# eCog106_BLED.net
KiCad netlist of a schematic drawn in EAGLE
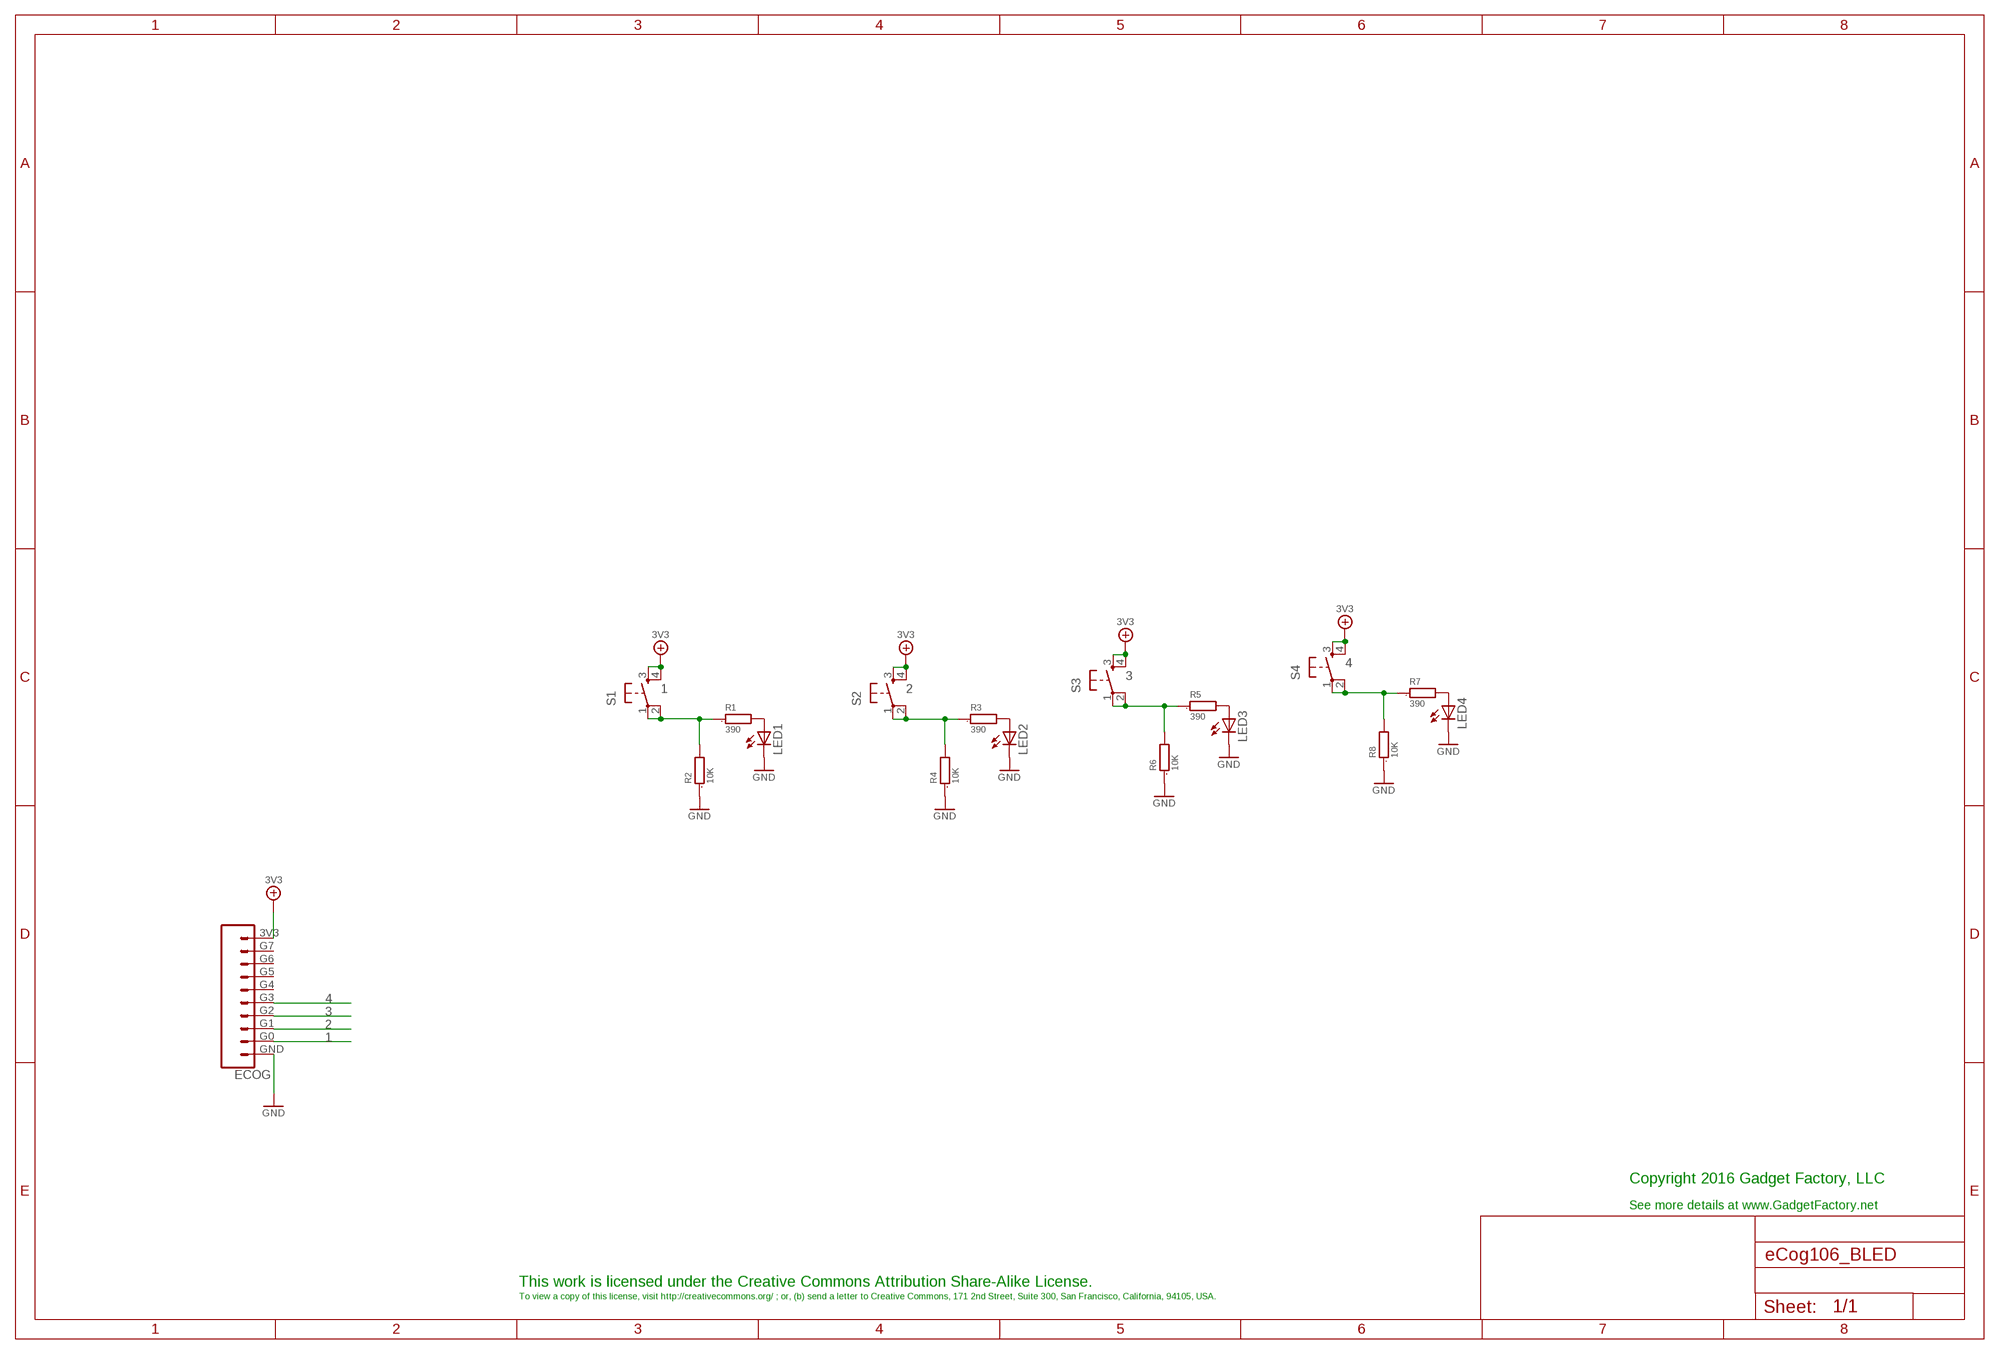
[diagram p0: schematic, sheet 1]

(export (version "E")
  (design (tool "Eeschema 10.0.6"))
  (components
    (comp (ref "ECOG")
      (value "ECOG_GENERAL_ROWECOG_GENERAL_SMD")
      (footprint "eagle-import:ECOG_GENERAL_SMD")
      (libsource (lib "eagle-import") (part "ECOG_GENERAL_ROWECOG_GENERAL_SMD"))
    )
    (comp (ref "LED1")
      (value "LEDCHIP-LED0805")
      (footprint "eagle-import:CHIP-LED0805")
      (libsource (lib "eagle-import") (part "LEDCHIP-LED0805"))
    )
    (comp (ref "LED2")
      (value "LEDCHIP-LED0805")
      (footprint "eagle-import:CHIP-LED0805")
      (libsource (lib "eagle-import") (part "LEDCHIP-LED0805"))
    )
    (comp (ref "LED3")
      (value "LEDCHIP-LED0805")
      (footprint "eagle-import:CHIP-LED0805")
      (libsource (lib "eagle-import") (part "LEDCHIP-LED0805"))
    )
    (comp (ref "LED4")
      (value "LEDCHIP-LED0805")
      (footprint "eagle-import:CHIP-LED0805")
      (libsource (lib "eagle-import") (part "LEDCHIP-LED0805"))
    )
    (comp (ref "R1")
      (value "390")
      (footprint "eagle-import:0805")
      (libsource (lib "eagle-import") (part "R0805"))
    )
    (comp (ref "R2")
      (value "10K")
      (footprint "eagle-import:0805")
      (libsource (lib "eagle-import") (part "R0805"))
    )
    (comp (ref "R3")
      (value "390")
      (footprint "eagle-import:0805")
      (libsource (lib "eagle-import") (part "R0805"))
    )
    (comp (ref "R4")
      (value "10K")
      (footprint "eagle-import:0805")
      (libsource (lib "eagle-import") (part "R0805"))
    )
    (comp (ref "R5")
      (value "390")
      (footprint "eagle-import:0805")
      (libsource (lib "eagle-import") (part "R0805"))
    )
    (comp (ref "R6")
      (value "10K")
      (footprint "eagle-import:0805")
      (libsource (lib "eagle-import") (part "R0805"))
    )
    (comp (ref "R7")
      (value "390")
      (footprint "eagle-import:0805")
      (libsource (lib "eagle-import") (part "R0805"))
    )
    (comp (ref "R8")
      (value "10K")
      (footprint "eagle-import:0805")
      (libsource (lib "eagle-import") (part "R0805"))
    )
    (comp (ref "S1")
      (value "TAC_SWITCHPTH")
      (footprint "eagle-import:TACTILE-PTH")
      (libsource (lib "eagle-import") (part "TAC_SWITCHPTH"))
    )
    (comp (ref "S2")
      (value "TAC_SWITCHPTH")
      (footprint "eagle-import:TACTILE-PTH")
      (libsource (lib "eagle-import") (part "TAC_SWITCHPTH"))
    )
    (comp (ref "S3")
      (value "TAC_SWITCHPTH")
      (footprint "eagle-import:TACTILE-PTH")
      (libsource (lib "eagle-import") (part "TAC_SWITCHPTH"))
    )
    (comp (ref "S4")
      (value "TAC_SWITCHPTH")
      (footprint "eagle-import:TACTILE-PTH")
      (libsource (lib "eagle-import") (part "TAC_SWITCHPTH"))
    )
  )
  (nets
    (net (code "1") (name "/1") (class "Default")
      (node (ref "ECOG") (pin "G0") (pinfunction "G0_G0") (pintype "passive"))
      (node (ref "R1") (pin "1") (pinfunction "1_1") (pintype "passive"))
      (node (ref "R2") (pin "2") (pinfunction "2_2") (pintype "passive"))
      (node (ref "S1") (pin "1") (pinfunction "1_1") (pintype "passive"))
      (node (ref "S1") (pin "2") (pinfunction "2_2") (pintype "passive"))
    )
    (net (code "2") (name "/2") (class "Default")
      (node (ref "ECOG") (pin "G1") (pinfunction "G1_G1") (pintype "passive"))
      (node (ref "R3") (pin "1") (pinfunction "1_1") (pintype "passive"))
      (node (ref "R4") (pin "2") (pinfunction "2_2") (pintype "passive"))
      (node (ref "S2") (pin "1") (pinfunction "1_1") (pintype "passive"))
      (node (ref "S2") (pin "2") (pinfunction "2_2") (pintype "passive"))
    )
    (net (code "3") (name "/3") (class "Default")
      (node (ref "ECOG") (pin "G2") (pinfunction "G2_G2") (pintype "passive"))
      (node (ref "R5") (pin "1") (pinfunction "1_1") (pintype "passive"))
      (node (ref "R6") (pin "2") (pinfunction "2_2") (pintype "passive"))
      (node (ref "S3") (pin "1") (pinfunction "1_1") (pintype "passive"))
      (node (ref "S3") (pin "2") (pinfunction "2_2") (pintype "passive"))
    )
    (net (code "4") (name "/4") (class "Default")
      (node (ref "ECOG") (pin "G3") (pinfunction "G3_G3") (pintype "passive"))
      (node (ref "R7") (pin "1") (pinfunction "1_1") (pintype "passive"))
      (node (ref "R8") (pin "2") (pinfunction "2_2") (pintype "passive"))
      (node (ref "S4") (pin "1") (pinfunction "1_1") (pintype "passive"))
      (node (ref "S4") (pin "2") (pinfunction "2_2") (pintype "passive"))
    )
    (net (code "5") (name "3V3") (class "Default")
      (node (ref "ECOG") (pin "3V3") (pinfunction "3V3_3V3") (pintype "power_in"))
      (node (ref "S1") (pin "3") (pinfunction "3_3") (pintype "passive"))
      (node (ref "S1") (pin "4") (pinfunction "4_4") (pintype "passive"))
      (node (ref "S2") (pin "3") (pinfunction "3_3") (pintype "passive"))
      (node (ref "S2") (pin "4") (pinfunction "4_4") (pintype "passive"))
      (node (ref "S3") (pin "3") (pinfunction "3_3") (pintype "passive"))
      (node (ref "S3") (pin "4") (pinfunction "4_4") (pintype "passive"))
      (node (ref "S4") (pin "3") (pinfunction "3_3") (pintype "passive"))
      (node (ref "S4") (pin "4") (pinfunction "4_4") (pintype "passive"))
    )
    (net (code "6") (name "GND") (class "Default")
      (node (ref "ECOG") (pin "GND") (pinfunction "GND_GND") (pintype "power_in"))
      (node (ref "LED1") (pin "C") (pinfunction "C_C") (pintype "passive"))
      (node (ref "LED2") (pin "C") (pinfunction "C_C") (pintype "passive"))
      (node (ref "LED3") (pin "C") (pinfunction "C_C") (pintype "passive"))
      (node (ref "LED4") (pin "C") (pinfunction "C_C") (pintype "passive"))
      (node (ref "R2") (pin "1") (pinfunction "1_1") (pintype "passive"))
      (node (ref "R4") (pin "1") (pinfunction "1_1") (pintype "passive"))
      (node (ref "R6") (pin "1") (pinfunction "1_1") (pintype "passive"))
      (node (ref "R8") (pin "1") (pinfunction "1_1") (pintype "passive"))
    )
    (net (code "7") (name "Net-(LED1-PadA)") (class "Default")
      (node (ref "LED1") (pin "A") (pinfunction "A_A") (pintype "passive"))
      (node (ref "R1") (pin "2") (pinfunction "2_2") (pintype "passive"))
    )
    (net (code "8") (name "Net-(LED2-PadA)") (class "Default")
      (node (ref "LED2") (pin "A") (pinfunction "A_A") (pintype "passive"))
      (node (ref "R3") (pin "2") (pinfunction "2_2") (pintype "passive"))
    )
    (net (code "9") (name "Net-(LED3-PadA)") (class "Default")
      (node (ref "LED3") (pin "A") (pinfunction "A_A") (pintype "passive"))
      (node (ref "R5") (pin "2") (pinfunction "2_2") (pintype "passive"))
    )
    (net (code "10") (name "Net-(LED4-PadA)") (class "Default")
      (node (ref "LED4") (pin "A") (pinfunction "A_A") (pintype "passive"))
      (node (ref "R7") (pin "2") (pinfunction "2_2") (pintype "passive"))
    )
    (net (code "11") (name "unconnected-(ECOG-PadG4)") (class "Default")
      (node (ref "ECOG") (pin "G4") (pinfunction "G4_G4") (pintype "passive"))
    )
    (net (code "12") (name "unconnected-(ECOG-PadG5)") (class "Default")
      (node (ref "ECOG") (pin "G5") (pinfunction "G5_G5") (pintype "passive"))
    )
    (net (code "13") (name "unconnected-(ECOG-PadG6)") (class "Default")
      (node (ref "ECOG") (pin "G6") (pinfunction "G6_G6") (pintype "passive"))
    )
    (net (code "14") (name "unconnected-(ECOG-PadG7)") (class "Default")
      (node (ref "ECOG") (pin "G7") (pinfunction "G7_G7") (pintype "passive"))
    )
  )
)
